# Core.net
KiCad netlist of a schematic drawn in Altium Designer
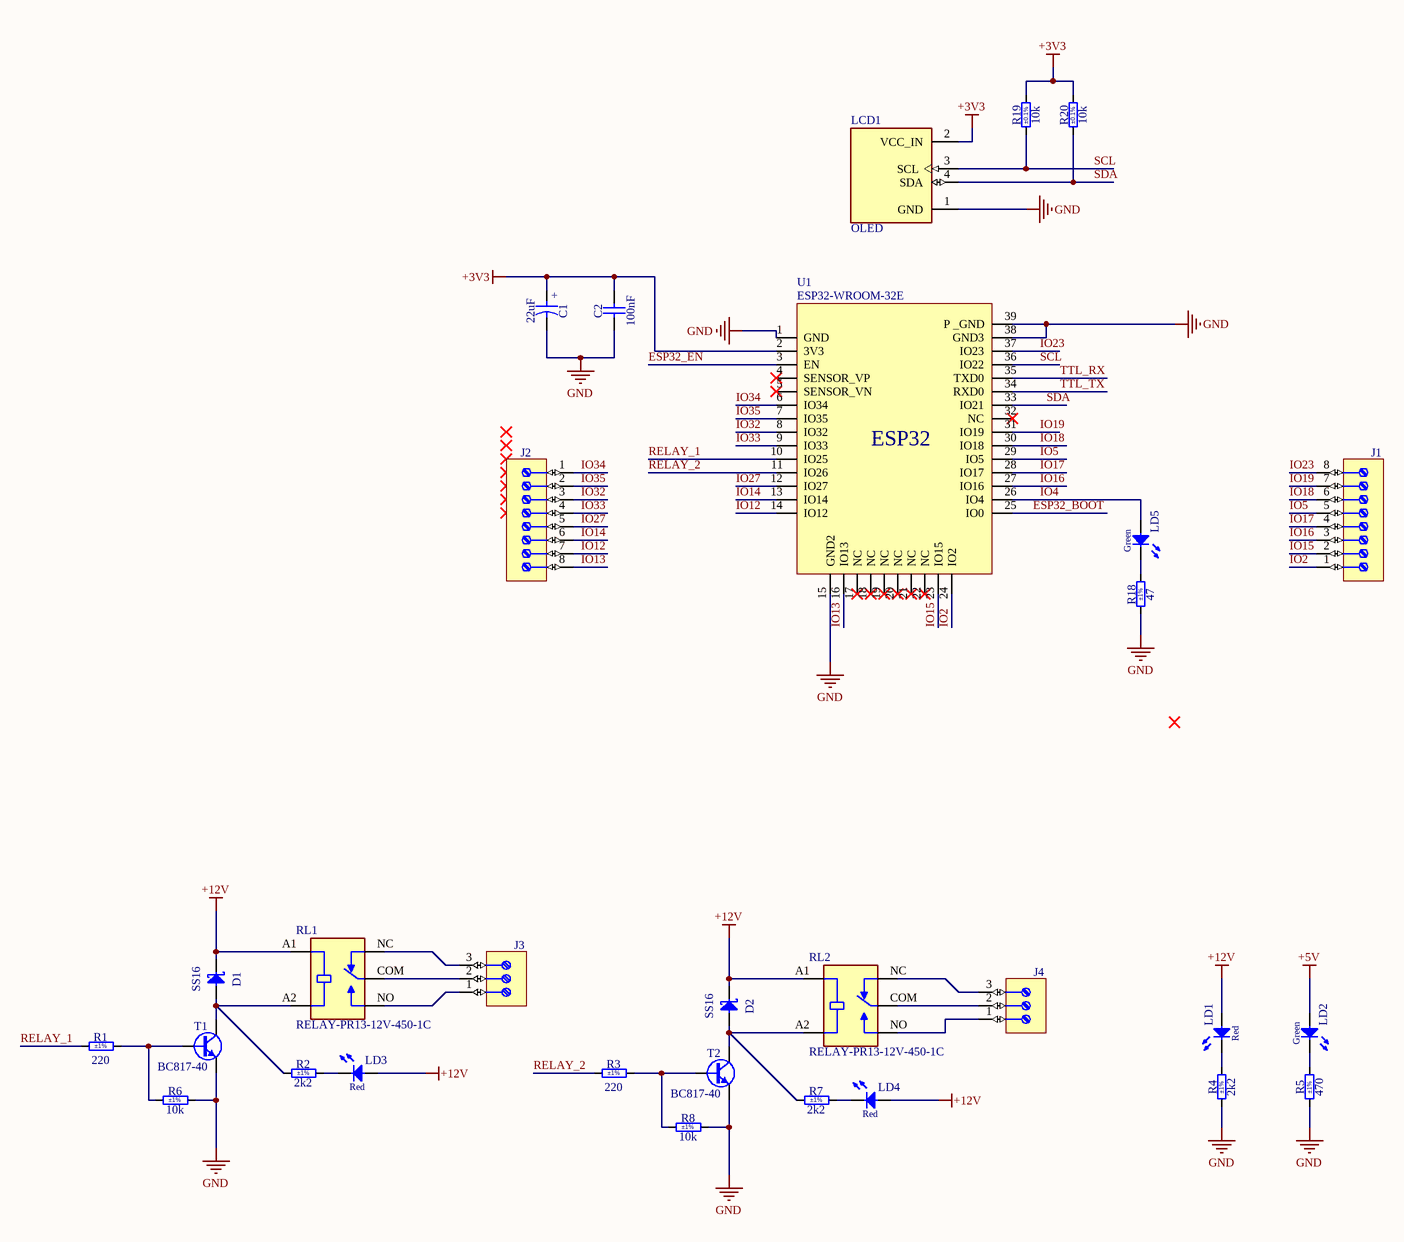
[diagram p0: Core.SchDoc]

(export (version "E")
  (design (tool "Eeschema 10.0.6"))
  (components
    (comp (ref "C1")
      (value "22uF")
      (footprint "CAPMP3528X210N")
      (description "Polarised capacitor")
      (fields
        (field (name "PART NUMBER") "CTE3528-21_22UF_10V_10%_LESR0700")
        (field (name "VOLTAGE") "10V")
        (field (name "AUTHOR") "CERN DEM JLC")
      )
      (libsource (lib "Capacitors") (part "Capacitor - polarized"))
    )
    (comp (ref "C2")
      (value "100nF")
      (footprint "CAPC1608X87N")
      (description "Non-polarised capacitor")
      (fields
        (field (name "PART NUMBER") "CC0603_100NF_50V_10%_X5R")
        (field (name "VOLTAGE") "50V")
        (field (name "AUTHOR") "CERN DEM MR")
      )
      (libsource (lib "Capacitors") (part "Capacitor - non polarized"))
    )
    (comp (ref "D1")
      (value "SS16")
      (footprint "DIOM5127X229N")
      (description "Schottky Diode")
      (fields
        (field (name "VOLTAGE") "60V")
        (field (name "POWER") "1A")
        (field (name "AUTHOR") "CERN DEM JLC")
      )
      (libsource (lib "ICs And Semiconductors") (part "Diode Schottky"))
    )
    (comp (ref "D2")
      (value "SS16")
      (footprint "DIOM5127X229N")
      (description "Schottky Diode")
      (fields
        (field (name "VOLTAGE") "60V")
        (field (name "POWER") "1A")
        (field (name "AUTHOR") "CERN DEM JLC")
      )
      (libsource (lib "ICs And Semiconductors") (part "Diode Schottky"))
    )
    (comp (ref "J1")
      (value "~")
      (footprint "PHOENIX_1715789")
      (description "Terminal Block, 8 Positions, Screw Connection")
      (fields
        (field (name "PART NUMBER") "PHOENIX_1715789")
        (field (name "MANUFACTURER") "PHOENIX CONTACT")
        (field (name "AUTHOR") "CERN DEM JMW")
      )
      (libsource (lib "") (part "Terminal Block_8 Positions_Screw Connection_1"))
    )
    (comp (ref "J2")
      (value "~")
      (footprint "PHOENIX_1715789")
      (description "Terminal Block, 8 Positions, Screw Connection")
      (fields
        (field (name "PART NUMBER") "PHOENIX_1715789")
        (field (name "MANUFACTURER") "PHOENIX CONTACT")
        (field (name "AUTHOR") "CERN DEM JMW")
      )
      (libsource (lib "Connectors") (part "Terminal Block_8 Positions_Screw Connection"))
    )
    (comp (ref "J3")
      (value "~")
      (footprint "PHOENIX_1715734")
      (description "Terminal Block, 3 Positions, Screw Connection")
      (fields
        (field (name "PART NUMBER") "PHOENIX_1715734")
        (field (name "MANUFACTURER") "PHOENIX CONTACT")
        (field (name "AUTHOR") "CERN DEM JLC")
      )
      (libsource (lib "Connectors") (part "Terminal Block_3 Positions_Screw Connection"))
    )
    (comp (ref "J4")
      (value "~")
      (footprint "PHOENIX_1715734")
      (description "Terminal Block, 3 Positions, Screw Connection")
      (fields
        (field (name "PART NUMBER") "PHOENIX_1715734")
        (field (name "MANUFACTURER") "PHOENIX CONTACT")
        (field (name "AUTHOR") "CERN DEM JLC")
      )
      (libsource (lib "Connectors") (part "Terminal Block_3 Positions_Screw Connection"))
    )
    (comp (ref "LCD1") (value "OLED") (footprint "OLED") (libsource (lib "Schlib1") (part "OLED SCREEN")))
    (comp (ref "LD1")
      (value "Red")
      (footprint "LED_KINGBRIGHT_KPH-1608SURCK")
      (description "LED Red 1C 2A")
      (fields
        (field (name "PART NUMBER") "LED_KINGBRIGHT_KPH-1608SURCK")
        (field (name "MANUFACTURER") "KINGBRIGHT")
        (field (name "AUTHOR") "CERN DEM JLC")
      )
      (libsource (lib "ICs And Semiconductors") (part "LED Red 1C 2A"))
    )
    (comp (ref "LD2")
      (value "Green")
      (footprint "LED_KINGBRIGHT_KP-1608CGCK")
      (description "LED Green 1C 2A")
      (fields
        (field (name "PART NUMBER") "LED_KINGBRIGHT_KP-1608CGCK")
        (field (name "MANUFACTURER") "KINGBRIGHT")
        (field (name "AUTHOR") "CERN DEM HF")
      )
      (libsource (lib "ICs And Semiconductors") (part "LED Green 1C 2A"))
    )
    (comp (ref "LD3")
      (value "Red")
      (footprint "LED_KINGBRIGHT_KPH-1608SURCK")
      (description "LED Red 1C 2A")
      (fields
        (field (name "PART NUMBER") "LED_KINGBRIGHT_KPH-1608SURCK")
        (field (name "MANUFACTURER") "KINGBRIGHT")
        (field (name "AUTHOR") "CERN DEM JLC")
      )
      (libsource (lib "ICs And Semiconductors") (part "LED Red 1C 2A"))
    )
    (comp (ref "LD4")
      (value "Red")
      (footprint "LED_KINGBRIGHT_KPH-1608SURCK")
      (description "LED Red 1C 2A")
      (fields
        (field (name "PART NUMBER") "LED_KINGBRIGHT_KPH-1608SURCK")
        (field (name "MANUFACTURER") "KINGBRIGHT")
        (field (name "AUTHOR") "CERN DEM JLC")
      )
      (libsource (lib "ICs And Semiconductors") (part "LED Red 1C 2A"))
    )
    (comp (ref "LD5")
      (value "Green")
      (footprint "LED_KINGBRIGHT_KP-1608CGCK")
      (description "LED Green 1C 2A")
      (fields
        (field (name "PART NUMBER") "LED_KINGBRIGHT_KP-1608CGCK")
        (field (name "MANUFACTURER") "KINGBRIGHT")
        (field (name "AUTHOR") "CERN DEM HF")
      )
      (libsource (lib "ICs And Semiconductors") (part "LED Green 1C 2A"))
    )
    (comp (ref "R1")
      (value "220")
      (footprint "RESC1608X55N")
      (description "Resistor - 1%")
      (fields
        (field (name "TOLERANCE") "±1%")
        (field (name "PART NUMBER") "R0603_220R_1%_0.1W_100PPM")
        (field (name "POWER") "0.1W")
        (field (name "AUTHOR") "CERN DEM JLC")
      )
      (libsource (lib "Resistors") (part "Resistor - 1%"))
    )
    (comp (ref "R2")
      (value "2k2")
      (footprint "RESC1608X55N")
      (description "Resistor - 1%")
      (fields
        (field (name "TOLERANCE") "±1%")
        (field (name "PART NUMBER") "R0603_2K2_1%_0.1W_100PPM")
        (field (name "POWER") "0.1W")
        (field (name "AUTHOR") "CERN DEM JLC")
      )
      (libsource (lib "Resistors") (part "Resistor - 1%"))
    )
    (comp (ref "R3")
      (value "220")
      (footprint "RESC1608X55N")
      (description "Resistor - 1%")
      (fields
        (field (name "TOLERANCE") "±1%")
        (field (name "PART NUMBER") "R0603_220R_1%_0.1W_100PPM")
        (field (name "POWER") "0.1W")
        (field (name "AUTHOR") "CERN DEM JLC")
      )
      (libsource (lib "Resistors") (part "Resistor - 1%"))
    )
    (comp (ref "R4")
      (value "2k2")
      (footprint "RESC1608X55N")
      (description "Resistor - 1%")
      (fields
        (field (name "TOLERANCE") "±1%")
        (field (name "PART NUMBER") "R0603_2K2_1%_0.1W_100PPM")
        (field (name "POWER") "0.1W")
        (field (name "AUTHOR") "CERN DEM JLC")
      )
      (libsource (lib "Resistors") (part "Resistor - 1%"))
    )
    (comp (ref "R5")
      (value "470")
      (footprint "RESC1608X55N")
      (description "Resistor - 1%")
      (fields
        (field (name "TOLERANCE") "±1%")
        (field (name "PART NUMBER") "R0603_470R_1%_0.1W_100PPM")
        (field (name "POWER") "0.1W")
        (field (name "AUTHOR") "CERN DEM JLC")
      )
      (libsource (lib "Resistors") (part "Resistor - 1%"))
    )
    (comp (ref "R6")
      (value "10k")
      (footprint "RESC1608X55N")
      (description "Resistor - 1%")
      (fields
        (field (name "TOLERANCE") "±1%")
        (field (name "PART NUMBER") "R0603_10K_1%_0.1W_100PPM")
        (field (name "POWER") "0.1W")
        (field (name "AUTHOR") "CERN DEM JLC")
      )
      (libsource (lib "Resistors") (part "Resistor - 1%"))
    )
    (comp (ref "R7")
      (value "2k2")
      (footprint "RESC1608X55N")
      (description "Resistor - 1%")
      (fields
        (field (name "TOLERANCE") "±1%")
        (field (name "PART NUMBER") "R0603_2K2_1%_0.1W_100PPM")
        (field (name "POWER") "0.1W")
        (field (name "AUTHOR") "CERN DEM JLC")
      )
      (libsource (lib "Resistors") (part "Resistor - 1%"))
    )
    (comp (ref "R8")
      (value "10k")
      (footprint "RESC1608X55N")
      (description "Resistor - 1%")
      (fields
        (field (name "TOLERANCE") "±1%")
        (field (name "PART NUMBER") "R0603_10K_1%_0.1W_100PPM")
        (field (name "POWER") "0.1W")
        (field (name "AUTHOR") "CERN DEM JLC")
      )
      (libsource (lib "Resistors") (part "Resistor - 1%"))
    )
    (comp (ref "R18")
      (value "47")
      (footprint "RESC1608X55N")
      (description "Resistor - 1%")
      (fields
        (field (name "TOLERANCE") "±1%")
        (field (name "PART NUMBER") "R0603_47R_1%_0.1W_100PPM")
        (field (name "POWER") "0.1W")
        (field (name "AUTHOR") "CERN DEM JLC")
      )
      (libsource (lib "Resistors") (part "Resistor - 1%"))
    )
    (comp (ref "R19")
      (value "10k")
      (footprint "RESC1608X55N")
      (description "Resistor - 0.1%")
      (fields
        (field (name "TOLERANCE") "±0.1%")
        (field (name "PART NUMBER") "R0603_10K_0.1%_0.063W_10PPM")
        (field (name "POWER") "0.063W")
        (field (name "AUTHOR") "CERN DEM JLC")
      )
      (libsource (lib "Resistors") (part "Resistor - 0.1%"))
    )
    (comp (ref "R20")
      (value "10k")
      (footprint "RESC1608X55N")
      (description "Resistor - 0.1%")
      (fields
        (field (name "TOLERANCE") "±0.1%")
        (field (name "PART NUMBER") "R0603_10K_0.1%_0.063W_10PPM")
        (field (name "POWER") "0.063W")
        (field (name "AUTHOR") "CERN DEM JLC")
      )
      (libsource (lib "Resistors") (part "Resistor - 0.1%"))
    )
    (comp (ref "RL1")
      (value "RELAY-PR13-12V-450-1C")
      (footprint "RELAY_PR13-12V-450-1C")
      (libsource (lib "Schlib1") (part "RELAY-PR13-12V-450-1C"))
    )
    (comp (ref "RL2")
      (value "RELAY-PR13-12V-450-1C")
      (footprint "RELAY_PR13-12V-450-1C")
      (libsource (lib "Schlib1") (part "RELAY-PR13-12V-450-1C"))
    )
    (comp (ref "T1")
      (value "BC817-40")
      (footprint "SOT95P230X110-3N")
      (description "NPN Transistor")
      (fields (field (name "MANUFACTURER") "NXP SEMICONDUCTORS") (field (name "AUTHOR") "CERN DEM BC"))
      (libsource (lib "ICs And Semiconductors") (part "NPN B1 E2 C3"))
    )
    (comp (ref "T2")
      (value "BC817-40")
      (footprint "SOT95P230X110-3N")
      (description "NPN Transistor")
      (fields (field (name "MANUFACTURER") "NXP SEMICONDUCTORS") (field (name "AUTHOR") "CERN DEM BC"))
      (libsource (lib "ICs And Semiconductors") (part "NPN B1 E2 C3"))
    )
    (comp (ref "U1")
      (value "ESP32-WROOM-32E")
      (footprint "ESP32")
      (libsource (lib "Schlib1") (part "ESP32-WROOM-32E"))
    )
  )
  (nets
    (net (code "1") (name "+3V3") (class "Default")
      (node (ref "C1") (pin "1") (pinfunction "1_1") (pintype "passive"))
      (node (ref "C2") (pin "2") (pinfunction "2_2") (pintype "passive"))
      (node (ref "LCD1") (pin "2") (pinfunction "VCC_IN_2") (pintype "power_in"))
      (node (ref "R19") (pin "2") (pinfunction "2_2") (pintype "passive"))
      (node (ref "R20") (pin "2") (pinfunction "2_2") (pintype "passive"))
      (node (ref "U1") (pin "2") (pinfunction "3V3_2") (pintype "passive"))
    )
    (net (code "2") (name "+5V") (class "Default")
      (node (ref "LD2") (pin "2") (pinfunction "A_2") (pintype "passive"))
    )
    (net (code "3") (name "+12V") (class "Default")
      (node (ref "D1") (pin "1") (pinfunction "C_1") (pintype "passive"))
      (node (ref "D2") (pin "1") (pinfunction "C_1") (pintype "passive"))
      (node (ref "LD1") (pin "2") (pinfunction "A_2") (pintype "passive"))
      (node (ref "LD3") (pin "2") (pinfunction "A_2") (pintype "passive"))
      (node (ref "LD4") (pin "2") (pinfunction "A_2") (pintype "passive"))
      (node (ref "RL1") (pin "A1") (pinfunction "COIL1_A1") (pintype "passive"))
      (node (ref "RL2") (pin "A1") (pinfunction "COIL1_A1") (pintype "passive"))
    )
    (net (code "4") (name "/ESP32_BOOT") (class "Default")
      (node (ref "U1") (pin "25") (pinfunction "IO0_25") (pintype "passive"))
    )
    (net (code "5") (name "/ESP32_EN") (class "Default")
      (node (ref "U1") (pin "3") (pinfunction "EN_3") (pintype "passive"))
    )
    (net (code "6") (name "/IO2") (class "Default")
      (node (ref "J1") (pin "1") (pinfunction "1_1") (pintype "bidirectional"))
      (node (ref "U1") (pin "24") (pinfunction "IO2_24") (pintype "passive"))
    )
    (net (code "7") (name "/IO4") (class "Default")
      (node (ref "LD5") (pin "2") (pinfunction "A_2") (pintype "passive"))
      (node (ref "U1") (pin "26") (pinfunction "IO4_26") (pintype "passive"))
    )
    (net (code "8") (name "/IO5") (class "Default")
      (node (ref "J1") (pin "5") (pinfunction "5_5") (pintype "bidirectional"))
      (node (ref "U1") (pin "29") (pinfunction "IO5_29") (pintype "passive"))
    )
    (net (code "9") (name "/IO12") (class "Default")
      (node (ref "J2") (pin "7") (pinfunction "7_7") (pintype "bidirectional"))
      (node (ref "U1") (pin "14") (pinfunction "IO12_14") (pintype "passive"))
    )
    (net (code "10") (name "/IO13") (class "Default")
      (node (ref "J2") (pin "8") (pinfunction "8_8") (pintype "bidirectional"))
      (node (ref "U1") (pin "16") (pinfunction "IO13_16") (pintype "passive"))
    )
    (net (code "11") (name "/IO14") (class "Default")
      (node (ref "J2") (pin "6") (pinfunction "6_6") (pintype "bidirectional"))
      (node (ref "U1") (pin "13") (pinfunction "IO14_13") (pintype "passive"))
    )
    (net (code "12") (name "/IO15") (class "Default")
      (node (ref "J1") (pin "2") (pinfunction "2_2") (pintype "bidirectional"))
      (node (ref "U1") (pin "23") (pinfunction "IO15_23") (pintype "passive"))
    )
    (net (code "13") (name "/IO16") (class "Default")
      (node (ref "J1") (pin "3") (pinfunction "3_3") (pintype "bidirectional"))
      (node (ref "U1") (pin "27") (pinfunction "IO16_27") (pintype "passive"))
    )
    (net (code "14") (name "/IO17") (class "Default")
      (node (ref "J1") (pin "4") (pinfunction "4_4") (pintype "bidirectional"))
      (node (ref "U1") (pin "28") (pinfunction "IO17_28") (pintype "passive"))
    )
    (net (code "15") (name "/IO18") (class "Default")
      (node (ref "J1") (pin "6") (pinfunction "6_6") (pintype "bidirectional"))
      (node (ref "U1") (pin "30") (pinfunction "IO18_30") (pintype "passive"))
    )
    (net (code "16") (name "/IO19") (class "Default")
      (node (ref "J1") (pin "7") (pinfunction "7_7") (pintype "bidirectional"))
      (node (ref "U1") (pin "31") (pinfunction "IO19_31") (pintype "passive"))
    )
    (net (code "17") (name "/IO23") (class "Default")
      (node (ref "J1") (pin "8") (pinfunction "8_8") (pintype "bidirectional"))
      (node (ref "U1") (pin "37") (pinfunction "IO23_37") (pintype "passive"))
    )
    (net (code "18") (name "/IO27") (class "Default")
      (node (ref "J2") (pin "5") (pinfunction "5_5") (pintype "bidirectional"))
      (node (ref "U1") (pin "12") (pinfunction "IO27_12") (pintype "passive"))
    )
    (net (code "19") (name "/IO32") (class "Default")
      (node (ref "J2") (pin "3") (pinfunction "3_3") (pintype "bidirectional"))
      (node (ref "U1") (pin "8") (pinfunction "IO32_8") (pintype "passive"))
    )
    (net (code "20") (name "/IO33") (class "Default")
      (node (ref "J2") (pin "4") (pinfunction "4_4") (pintype "bidirectional"))
      (node (ref "U1") (pin "9") (pinfunction "IO33_9") (pintype "passive"))
    )
    (net (code "21") (name "/IO34") (class "Default")
      (node (ref "J2") (pin "1") (pinfunction "1_1") (pintype "bidirectional"))
      (node (ref "U1") (pin "6") (pinfunction "IO34_6") (pintype "passive"))
    )
    (net (code "22") (name "/IO35") (class "Default")
      (node (ref "J2") (pin "2") (pinfunction "2_2") (pintype "bidirectional"))
      (node (ref "U1") (pin "7") (pinfunction "IO35_7") (pintype "passive"))
    )
    (net (code "23") (name "/RELAY_1") (class "Default")
      (node (ref "R1") (pin "1") (pinfunction "1_1") (pintype "passive"))
      (node (ref "U1") (pin "10") (pinfunction "IO25_10") (pintype "passive"))
    )
    (net (code "24") (name "/RELAY_2") (class "Default")
      (node (ref "R3") (pin "1") (pinfunction "1_1") (pintype "passive"))
      (node (ref "U1") (pin "11") (pinfunction "IO26_11") (pintype "passive"))
    )
    (net (code "25") (name "/SCL") (class "Default")
      (node (ref "LCD1") (pin "3") (pinfunction "SCL_3") (pintype "input"))
      (node (ref "R19") (pin "1") (pinfunction "1_1") (pintype "passive"))
      (node (ref "U1") (pin "36") (pinfunction "IO22_36") (pintype "passive"))
    )
    (net (code "26") (name "/SDA") (class "Default")
      (node (ref "LCD1") (pin "4") (pinfunction "SDA_4") (pintype "bidirectional"))
      (node (ref "R20") (pin "1") (pinfunction "1_1") (pintype "passive"))
      (node (ref "U1") (pin "33") (pinfunction "IO21_33") (pintype "passive"))
    )
    (net (code "27") (name "/TTL_RX") (class "Default")
      (node (ref "U1") (pin "35") (pinfunction "TXD0_35") (pintype "passive"))
    )
    (net (code "28") (name "/TTL_TX") (class "Default")
      (node (ref "U1") (pin "34") (pinfunction "RXD0_34") (pintype "passive"))
    )
    (net (code "29") (name "GND") (class "Default")
      (node (ref "C1") (pin "2") (pinfunction "2_2") (pintype "passive"))
      (node (ref "C2") (pin "1") (pinfunction "1_1") (pintype "passive"))
      (node (ref "LCD1") (pin "1") (pinfunction "GND_1") (pintype "power_in"))
      (node (ref "R18") (pin "1") (pinfunction "1_1") (pintype "passive"))
      (node (ref "R4") (pin "1") (pinfunction "1_1") (pintype "passive"))
      (node (ref "R5") (pin "1") (pinfunction "1_1") (pintype "passive"))
      (node (ref "R6") (pin "2") (pinfunction "2_2") (pintype "passive"))
      (node (ref "R8") (pin "2") (pinfunction "2_2") (pintype "passive"))
      (node (ref "T1") (pin "2") (pinfunction "E_2") (pintype "passive"))
      (node (ref "T2") (pin "2") (pinfunction "E_2") (pintype "passive"))
      (node (ref "U1") (pin "1") (pinfunction "GND_1") (pintype "passive"))
      (node (ref "U1") (pin "15") (pinfunction "GND2_15") (pintype "passive"))
      (node (ref "U1") (pin "38") (pinfunction "GND3_38") (pintype "passive"))
      (node (ref "U1") (pin "39") (pinfunction "P__GND_39") (pintype "passive"))
    )
    (net (code "30") (name "Net-(D1-A)") (class "Default")
      (node (ref "D1") (pin "2") (pinfunction "A_2") (pintype "passive"))
      (node (ref "R2") (pin "1") (pinfunction "1_1") (pintype "passive"))
      (node (ref "RL1") (pin "A2") (pinfunction "COIL2_A2") (pintype "passive"))
      (node (ref "T1") (pin "3") (pinfunction "C_3") (pintype "passive"))
    )
    (net (code "31") (name "Net-(D2-A)") (class "Default")
      (node (ref "D2") (pin "2") (pinfunction "A_2") (pintype "passive"))
      (node (ref "R7") (pin "1") (pinfunction "1_1") (pintype "passive"))
      (node (ref "RL2") (pin "A2") (pinfunction "COIL2_A2") (pintype "passive"))
      (node (ref "T2") (pin "3") (pinfunction "C_3") (pintype "passive"))
    )
    (net (code "32") (name "Net-(J3-Pad1)") (class "Default")
      (node (ref "J3") (pin "1") (pinfunction "1_1") (pintype "bidirectional"))
      (node (ref "RL1") (pin "NO") (pinfunction "NO_NO") (pintype "passive"))
    )
    (net (code "33") (name "Net-(J3-Pad2)") (class "Default")
      (node (ref "J3") (pin "2") (pinfunction "2_2") (pintype "bidirectional"))
      (node (ref "RL1") (pin "COM") (pinfunction "COM_COM") (pintype "passive"))
    )
    (net (code "34") (name "Net-(J3-Pad3)") (class "Default")
      (node (ref "J3") (pin "3") (pinfunction "3_3") (pintype "bidirectional"))
      (node (ref "RL1") (pin "NC") (pinfunction "NC_NC") (pintype "passive"))
    )
    (net (code "35") (name "Net-(J4-Pad1)") (class "Default")
      (node (ref "J4") (pin "1") (pinfunction "1_1") (pintype "bidirectional"))
      (node (ref "RL2") (pin "NO") (pinfunction "NO_NO") (pintype "passive"))
    )
    (net (code "36") (name "Net-(J4-Pad2)") (class "Default")
      (node (ref "J4") (pin "2") (pinfunction "2_2") (pintype "bidirectional"))
      (node (ref "RL2") (pin "COM") (pinfunction "COM_COM") (pintype "passive"))
    )
    (net (code "37") (name "Net-(J4-Pad3)") (class "Default")
      (node (ref "J4") (pin "3") (pinfunction "3_3") (pintype "bidirectional"))
      (node (ref "RL2") (pin "NC") (pinfunction "NC_NC") (pintype "passive"))
    )
    (net (code "38") (name "Net-(LD1-C)") (class "Default")
      (node (ref "LD1") (pin "1") (pinfunction "C_1") (pintype "passive"))
      (node (ref "R4") (pin "2") (pinfunction "2_2") (pintype "passive"))
    )
    (net (code "39") (name "Net-(LD2-C)") (class "Default")
      (node (ref "LD2") (pin "1") (pinfunction "C_1") (pintype "passive"))
      (node (ref "R5") (pin "2") (pinfunction "2_2") (pintype "passive"))
    )
    (net (code "40") (name "Net-(LD3-C)") (class "Default")
      (node (ref "LD3") (pin "1") (pinfunction "C_1") (pintype "passive"))
      (node (ref "R2") (pin "2") (pinfunction "2_2") (pintype "passive"))
    )
    (net (code "41") (name "Net-(LD4-C)") (class "Default")
      (node (ref "LD4") (pin "1") (pinfunction "C_1") (pintype "passive"))
      (node (ref "R7") (pin "2") (pinfunction "2_2") (pintype "passive"))
    )
    (net (code "42") (name "Net-(LD5-C)") (class "Default")
      (node (ref "LD5") (pin "1") (pinfunction "C_1") (pintype "passive"))
      (node (ref "R18") (pin "2") (pinfunction "2_2") (pintype "passive"))
    )
    (net (code "43") (name "Net-(T1-B)") (class "Default")
      (node (ref "R1") (pin "2") (pinfunction "2_2") (pintype "passive"))
      (node (ref "R6") (pin "1") (pinfunction "1_1") (pintype "passive"))
      (node (ref "T1") (pin "1") (pinfunction "B_1") (pintype "passive"))
    )
    (net (code "44") (name "Net-(T2-B)") (class "Default")
      (node (ref "R3") (pin "2") (pinfunction "2_2") (pintype "passive"))
      (node (ref "R8") (pin "1") (pinfunction "1_1") (pintype "passive"))
      (node (ref "T2") (pin "1") (pinfunction "B_1") (pintype "passive"))
    )
    (net (code "45") (name "unconnected-(U1-NC-Pad17)") (class "Default")
      (node (ref "U1") (pin "17") (pinfunction "NC_17") (pintype "passive+no_connect"))
    )
    (net (code "46") (name "unconnected-(U1-NC-Pad18)") (class "Default")
      (node (ref "U1") (pin "18") (pinfunction "NC_18") (pintype "passive+no_connect"))
    )
    (net (code "47") (name "unconnected-(U1-NC-Pad19)") (class "Default")
      (node (ref "U1") (pin "19") (pinfunction "NC_19") (pintype "passive+no_connect"))
    )
    (net (code "48") (name "unconnected-(U1-NC-Pad20)") (class "Default")
      (node (ref "U1") (pin "20") (pinfunction "NC_20") (pintype "passive+no_connect"))
    )
    (net (code "49") (name "unconnected-(U1-NC-Pad21)") (class "Default")
      (node (ref "U1") (pin "21") (pinfunction "NC_21") (pintype "passive+no_connect"))
    )
    (net (code "50") (name "unconnected-(U1-NC-Pad22)") (class "Default")
      (node (ref "U1") (pin "22") (pinfunction "NC_22") (pintype "passive+no_connect"))
    )
    (net (code "51") (name "unconnected-(U1-NC-Pad32)") (class "Default")
      (node (ref "U1") (pin "32") (pinfunction "NC_32") (pintype "passive+no_connect"))
    )
    (net (code "52") (name "unconnected-(U1-SENSOR_VN-Pad5)") (class "Default")
      (node (ref "U1") (pin "5") (pinfunction "SENSOR_VN_5") (pintype "passive+no_connect"))
    )
    (net (code "53") (name "unconnected-(U1-SENSOR_VP-Pad4)") (class "Default")
      (node (ref "U1") (pin "4") (pinfunction "SENSOR_VP_4") (pintype "passive+no_connect"))
    )
  )
)
